# chujograj.net
KiCad netlist of a schematic drawn in EAGLE
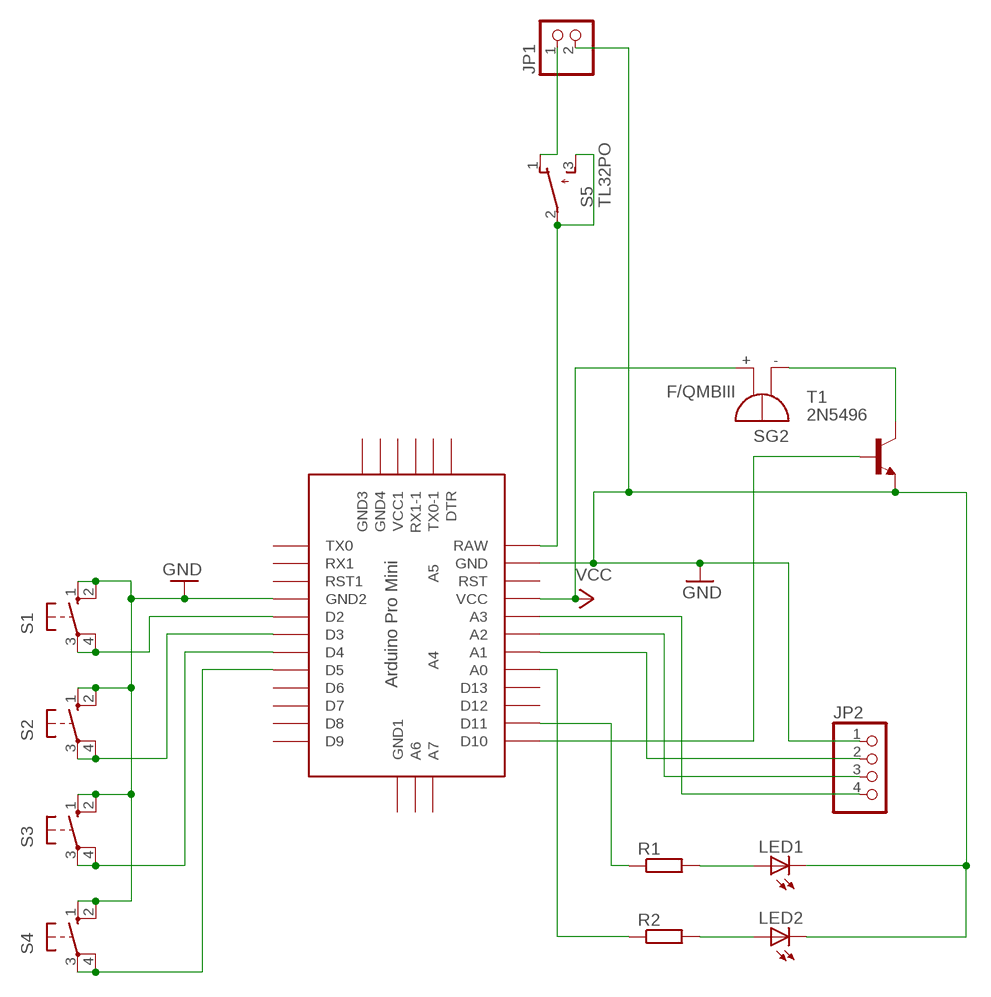
[diagram p0: schematic, sheet 1]

(export (version "E")
  (design (tool "Eeschema 10.0.6"))
  (components
    (comp (ref "JP1")
      (value "PINHD-1X2")
      (footprint "eagle-import:1X02")
      (libsource (lib "eagle-import") (part "PINHD-1X2"))
    )
    (comp (ref "JP2")
      (value "PINHD-1X4")
      (footprint "eagle-import:1X04")
      (libsource (lib "eagle-import") (part "PINHD-1X4"))
    )
    (comp (ref "LED1")
      (value "LED5MM")
      (footprint "eagle-import:LED5MM")
      (libsource (lib "eagle-import") (part "LED5MM"))
    )
    (comp (ref "LED2")
      (value "LED5MM")
      (footprint "eagle-import:LED5MM")
      (libsource (lib "eagle-import") (part "LED5MM"))
    )
    (comp (ref "R1")
      (value "R-EU_0207/10")
      (footprint "eagle-import:0207_10")
      (libsource (lib "eagle-import") (part "R-EU_0207/10"))
    )
    (comp (ref "R2")
      (value "R-EU_0207/10")
      (footprint "eagle-import:0207_10")
      (libsource (lib "eagle-import") (part "R-EU_0207/10"))
    )
    (comp (ref "S1")
      (value "40-XX")
      (footprint "eagle-import:B3F-40XX")
      (fields (field (name "MF") "OMRON COMPONENTS USA") (field (name "MPN") "B3F-4000"))
      (libsource (lib "eagle-import") (part "40-XX"))
    )
    (comp (ref "S2")
      (value "40-XX")
      (footprint "eagle-import:B3F-40XX")
      (fields (field (name "MF") "OMRON COMPONENTS USA") (field (name "MPN") "B3F-4000"))
      (libsource (lib "eagle-import") (part "40-XX"))
    )
    (comp (ref "S3")
      (value "40-XX")
      (footprint "eagle-import:B3F-40XX")
      (fields (field (name "MF") "OMRON COMPONENTS USA") (field (name "MPN") "B3F-4000"))
      (libsource (lib "eagle-import") (part "40-XX"))
    )
    (comp (ref "S4")
      (value "40-XX")
      (footprint "eagle-import:B3F-40XX")
      (fields (field (name "MF") "OMRON COMPONENTS USA") (field (name "MPN") "B3F-4000"))
      (libsource (lib "eagle-import") (part "40-XX"))
    )
    (comp (ref "S5")
      (value "TL32PO")
      (footprint "eagle-import:TL3XPO")
      (libsource (lib "eagle-import") (part "TL32PO"))
    )
    (comp (ref "SG2")
      (value "F/QMBIII")
      (footprint "eagle-import:F_QMBIII")
      (libsource (lib "eagle-import") (part "F/QMBIII"))
    )
    (comp (ref "T1")
      (value "2N5496")
      (footprint "eagle-import:TO220")
      (libsource (lib "eagle-import") (part "2N5496"))
    )
    (comp (ref "U$1")
      (value "ABK-PRO-MINI")
      (footprint "eagle-import:ABK-PRO-MINI")
      (libsource (lib "eagle-import") (part "ABK-PRO-MINI"))
    )
  )
  (nets
    (net (code "1") (name "GND") (class "Default")
      (node (ref "JP1") (pin "2") (pinfunction "2_2") (pintype "passive"))
      (node (ref "JP2") (pin "1") (pinfunction "1_1") (pintype "passive"))
      (node (ref "LED1") (pin "K") (pinfunction "C_K") (pintype "passive"))
      (node (ref "LED2") (pin "K") (pinfunction "C_K") (pintype "passive"))
      (node (ref "S1") (pin "1") (pinfunction "S_1") (pintype "passive"))
      (node (ref "S1") (pin "2") (pinfunction "S1_2") (pintype "passive"))
      (node (ref "S2") (pin "1") (pinfunction "S_1") (pintype "passive"))
      (node (ref "S2") (pin "2") (pinfunction "S1_2") (pintype "passive"))
      (node (ref "S3") (pin "1") (pinfunction "S_1") (pintype "passive"))
      (node (ref "S3") (pin "2") (pinfunction "S1_2") (pintype "passive"))
      (node (ref "S4") (pin "1") (pinfunction "S_1") (pintype "passive"))
      (node (ref "S4") (pin "2") (pinfunction "S1_2") (pintype "passive"))
      (node (ref "T1") (pin "3") (pinfunction "E_3") (pintype "passive"))
      (node (ref "U$1") (pin "GND") (pinfunction "GND_GND") (pintype "bidirectional"))
      (node (ref "U$1") (pin "GND1") (pinfunction "GND2_GND1") (pintype "bidirectional"))
    )
    (net (code "2") (name "Net-(JP2-Pad2)") (class "Default")
      (node (ref "JP2") (pin "2") (pinfunction "2_2") (pintype "passive"))
      (node (ref "U$1") (pin "A1") (pinfunction "A1_A1") (pintype "bidirectional"))
    )
    (net (code "3") (name "Net-(JP2-Pad3)") (class "Default")
      (node (ref "JP2") (pin "3") (pinfunction "3_3") (pintype "passive"))
      (node (ref "U$1") (pin "A2") (pinfunction "A2_A2") (pintype "bidirectional"))
    )
    (net (code "4") (name "Net-(JP2-Pad4)") (class "Default")
      (node (ref "JP2") (pin "4") (pinfunction "4_4") (pintype "passive"))
      (node (ref "U$1") (pin "A3") (pinfunction "A3_A3") (pintype "bidirectional"))
    )
    (net (code "5") (name "Net-(LED1-PadA)") (class "Default")
      (node (ref "LED1") (pin "A") (pinfunction "A_A") (pintype "passive"))
      (node (ref "R1") (pin "2") (pinfunction "2_2") (pintype "passive"))
    )
    (net (code "6") (name "Net-(LED2-PadA)") (class "Default")
      (node (ref "LED2") (pin "A") (pinfunction "A_A") (pintype "passive"))
      (node (ref "R2") (pin "2") (pinfunction "2_2") (pintype "passive"))
    )
    (net (code "7") (name "Net-(R1-Pad1)") (class "Default")
      (node (ref "R1") (pin "1") (pinfunction "1_1") (pintype "passive"))
      (node (ref "U$1") (pin "D11") (pinfunction "D11_D11") (pintype "bidirectional"))
    )
    (net (code "8") (name "Net-(R2-Pad1)") (class "Default")
      (node (ref "R2") (pin "1") (pinfunction "1_1") (pintype "passive"))
      (node (ref "U$1") (pin "A0") (pinfunction "A0_A0") (pintype "bidirectional"))
    )
    (net (code "9") (name "Net-(S1-P)") (class "Default")
      (node (ref "S1") (pin "3") (pinfunction "P_3") (pintype "passive"))
      (node (ref "S1") (pin "4") (pinfunction "P1_4") (pintype "passive"))
      (node (ref "U$1") (pin "D2") (pinfunction "D2_D2") (pintype "bidirectional"))
    )
    (net (code "10") (name "Net-(S2-P)") (class "Default")
      (node (ref "S2") (pin "3") (pinfunction "P_3") (pintype "passive"))
      (node (ref "S2") (pin "4") (pinfunction "P1_4") (pintype "passive"))
      (node (ref "U$1") (pin "D3") (pinfunction "D3_D3") (pintype "bidirectional"))
    )
    (net (code "11") (name "Net-(S3-P)") (class "Default")
      (node (ref "S3") (pin "3") (pinfunction "P_3") (pintype "passive"))
      (node (ref "S3") (pin "4") (pinfunction "P1_4") (pintype "passive"))
      (node (ref "U$1") (pin "D4") (pinfunction "D4_D4") (pintype "bidirectional"))
    )
    (net (code "12") (name "Net-(S4-P)") (class "Default")
      (node (ref "S4") (pin "3") (pinfunction "P_3") (pintype "passive"))
      (node (ref "S4") (pin "4") (pinfunction "P1_4") (pintype "passive"))
      (node (ref "U$1") (pin "D5") (pinfunction "D5_D5") (pintype "bidirectional"))
    )
    (net (code "13") (name "Net-(S5-O)") (class "Default")
      (node (ref "JP1") (pin "1") (pinfunction "1_1") (pintype "passive"))
      (node (ref "S5") (pin "1") (pinfunction "O_1") (pintype "passive"))
    )
    (net (code "14") (name "Net-(S5-P)") (class "Default")
      (node (ref "S5") (pin "2") (pinfunction "P_2") (pintype "passive"))
      (node (ref "S5") (pin "3") (pinfunction "S_3") (pintype "passive"))
      (node (ref "U$1") (pin "RAW") (pinfunction "RAW_RAW") (pintype "bidirectional"))
    )
    (net (code "15") (name "Net-(SG2-+)") (class "Default")
      (node (ref "SG2") (pin "-") (pinfunction "+_-") (pintype "passive"))
      (node (ref "T1") (pin "2") (pinfunction "C_2") (pintype "passive"))
    )
    (net (code "16") (name "Net-(T1-B)") (class "Default")
      (node (ref "T1") (pin "1") (pinfunction "B_1") (pintype "passive"))
      (node (ref "U$1") (pin "D10") (pinfunction "D10_D10") (pintype "bidirectional"))
    )
    (net (code "17") (name "VCC") (class "Default")
      (node (ref "SG2") (pin "+") (pinfunction "-_+") (pintype "passive"))
      (node (ref "U$1") (pin "VCC") (pinfunction "VCC_VCC") (pintype "bidirectional"))
    )
    (net (code "18") (name "unconnected-(U$1-GND1-PadGND4)") (class "Default")
      (node (ref "U$1") (pin "GND4") (pinfunction "GND1_GND4") (pintype "bidirectional"))
    )
    (net (code "19") (name "unconnected-(U$1-GND3-PadGND2)") (class "Default")
      (node (ref "U$1") (pin "GND2") (pinfunction "GND3_GND2") (pintype "bidirectional"))
    )
    (net (code "20") (name "unconnected-(U$1-GND4-PadGND3)") (class "Default")
      (node (ref "U$1") (pin "GND3") (pinfunction "GND4_GND3") (pintype "bidirectional"))
    )
    (net (code "21") (name "unconnected-(U$1-PadA4)") (class "Default")
      (node (ref "U$1") (pin "A4") (pinfunction "A4_A4") (pintype "bidirectional"))
    )
    (net (code "22") (name "unconnected-(U$1-PadA5)") (class "Default")
      (node (ref "U$1") (pin "A5") (pinfunction "A5_A5") (pintype "bidirectional"))
    )
    (net (code "23") (name "unconnected-(U$1-PadA6)") (class "Default")
      (node (ref "U$1") (pin "A6") (pinfunction "A6_A6") (pintype "bidirectional"))
    )
    (net (code "24") (name "unconnected-(U$1-PadA7)") (class "Default")
      (node (ref "U$1") (pin "A7") (pinfunction "A7_A7") (pintype "bidirectional"))
    )
    (net (code "25") (name "unconnected-(U$1-PadD6)") (class "Default")
      (node (ref "U$1") (pin "D6") (pinfunction "D6_D6") (pintype "bidirectional"))
    )
    (net (code "26") (name "unconnected-(U$1-PadD7)") (class "Default")
      (node (ref "U$1") (pin "D7") (pinfunction "D7_D7") (pintype "bidirectional"))
    )
    (net (code "27") (name "unconnected-(U$1-PadD8)") (class "Default")
      (node (ref "U$1") (pin "D8") (pinfunction "D8_D8") (pintype "bidirectional"))
    )
    (net (code "28") (name "unconnected-(U$1-PadD9)") (class "Default")
      (node (ref "U$1") (pin "D9") (pinfunction "D9_D9") (pintype "bidirectional"))
    )
    (net (code "29") (name "unconnected-(U$1-PadD12)") (class "Default")
      (node (ref "U$1") (pin "D12") (pinfunction "D12_D12") (pintype "bidirectional"))
    )
    (net (code "30") (name "unconnected-(U$1-PadD13)") (class "Default")
      (node (ref "U$1") (pin "D13") (pinfunction "D13_D13") (pintype "bidirectional"))
    )
    (net (code "31") (name "unconnected-(U$1-PadDTR)") (class "Default")
      (node (ref "U$1") (pin "DTR") (pinfunction "DTR_DTR") (pintype "bidirectional"))
    )
    (net (code "32") (name "unconnected-(U$1-PadRST)") (class "Default")
      (node (ref "U$1") (pin "RST") (pinfunction "RST_RST") (pintype "bidirectional"))
    )
    (net (code "33") (name "unconnected-(U$1-PadRST1)") (class "Default")
      (node (ref "U$1") (pin "RST1") (pinfunction "RST1_RST1") (pintype "bidirectional"))
    )
    (net (code "34") (name "unconnected-(U$1-PadRX1)") (class "Default")
      (node (ref "U$1") (pin "RX1") (pinfunction "RX1_RX1") (pintype "bidirectional"))
    )
    (net (code "35") (name "unconnected-(U$1-PadRX1-1)") (class "Default")
      (node (ref "U$1") (pin "RX1-1") (pinfunction "RX1-1_RX1-1") (pintype "bidirectional"))
    )
    (net (code "36") (name "unconnected-(U$1-PadTX0)") (class "Default")
      (node (ref "U$1") (pin "TX0") (pinfunction "TX0_TX0") (pintype "bidirectional"))
    )
    (net (code "37") (name "unconnected-(U$1-PadTX0-1)") (class "Default")
      (node (ref "U$1") (pin "TX0-1") (pinfunction "TX0-1_TX0-1") (pintype "bidirectional"))
    )
    (net (code "38") (name "unconnected-(U$1-PadVCC1)") (class "Default")
      (node (ref "U$1") (pin "VCC1") (pinfunction "VCC1_VCC1") (pintype "bidirectional"))
    )
  )
)
